# BV100011_ControlMemory.net
KiCad netlist of a schematic drawn in Altium Designer
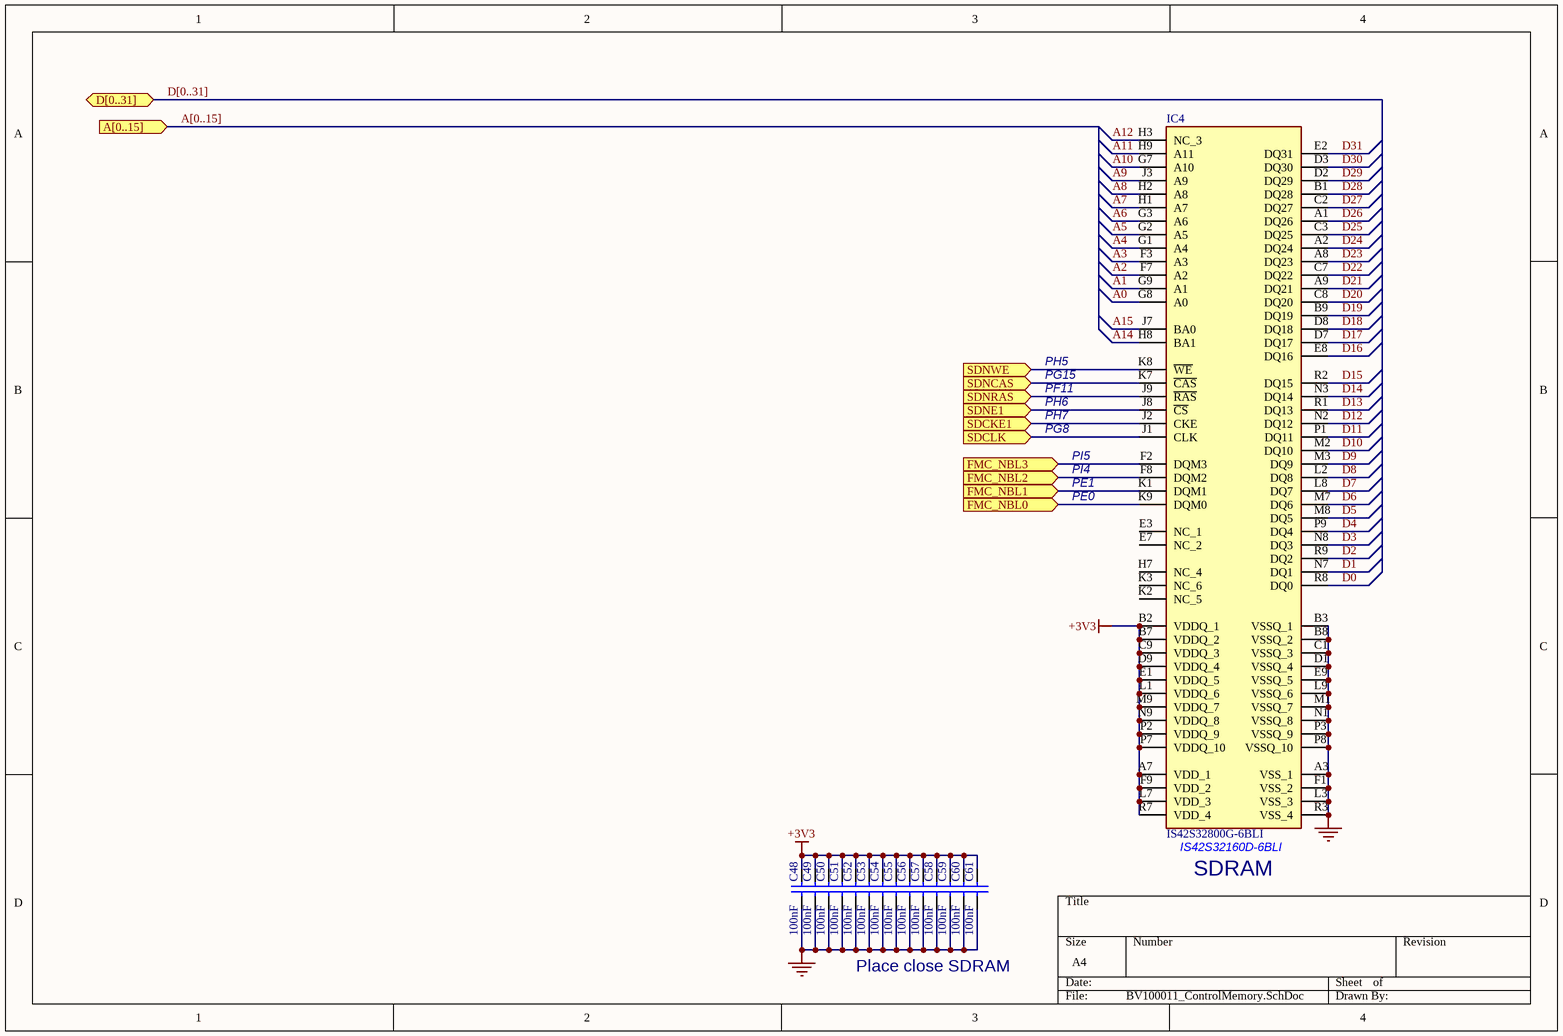
[diagram p0: BV100011_ControlMemory.SchDoc]

(export (version "E")
  (design (tool "Eeschema 10.0.6"))
  (components
    (comp (ref "C48")
      (value "100nF")
      (footprint "C0603")
      (description "Capacitor")
      (fields (field (name "PUBLISHER") "Altium Limited"))
      (libsource (lib "Miscellaneous Devices") (part "Cap"))
    )
    (comp (ref "C49")
      (value "100nF")
      (footprint "C0603")
      (description "Capacitor")
      (fields (field (name "PUBLISHER") "Altium Limited"))
      (libsource (lib "Miscellaneous Devices") (part "Cap"))
    )
    (comp (ref "C50")
      (value "100nF")
      (footprint "C0603")
      (description "Capacitor")
      (fields (field (name "PUBLISHER") "Altium Limited"))
      (libsource (lib "Miscellaneous Devices") (part "Cap"))
    )
    (comp (ref "C51")
      (value "100nF")
      (footprint "C0603")
      (description "Capacitor")
      (fields (field (name "PUBLISHER") "Altium Limited"))
      (libsource (lib "Miscellaneous Devices") (part "Cap"))
    )
    (comp (ref "C52")
      (value "100nF")
      (footprint "C0603")
      (description "Capacitor")
      (fields (field (name "PUBLISHER") "Altium Limited"))
      (libsource (lib "Miscellaneous Devices") (part "Cap"))
    )
    (comp (ref "C53")
      (value "100nF")
      (footprint "C0603")
      (description "Capacitor")
      (fields (field (name "PUBLISHER") "Altium Limited"))
      (libsource (lib "Miscellaneous Devices") (part "Cap"))
    )
    (comp (ref "C54")
      (value "100nF")
      (footprint "C0603")
      (description "Capacitor")
      (fields (field (name "PUBLISHER") "Altium Limited"))
      (libsource (lib "Miscellaneous Devices") (part "Cap"))
    )
    (comp (ref "C55")
      (value "100nF")
      (footprint "C0603")
      (description "Capacitor")
      (fields (field (name "PUBLISHER") "Altium Limited"))
      (libsource (lib "Miscellaneous Devices") (part "Cap"))
    )
    (comp (ref "C56")
      (value "100nF")
      (footprint "C0603")
      (description "Capacitor")
      (fields (field (name "PUBLISHER") "Altium Limited"))
      (libsource (lib "Miscellaneous Devices") (part "Cap"))
    )
    (comp (ref "C57")
      (value "100nF")
      (footprint "C0603")
      (description "Capacitor")
      (fields (field (name "PUBLISHER") "Altium Limited"))
      (libsource (lib "Miscellaneous Devices") (part "Cap"))
    )
    (comp (ref "C58")
      (value "100nF")
      (footprint "C0603")
      (description "Capacitor")
      (fields (field (name "PUBLISHER") "Altium Limited"))
      (libsource (lib "Miscellaneous Devices") (part "Cap"))
    )
    (comp (ref "C59")
      (value "100nF")
      (footprint "C0603")
      (description "Capacitor")
      (fields (field (name "PUBLISHER") "Altium Limited"))
      (libsource (lib "Miscellaneous Devices") (part "Cap"))
    )
    (comp (ref "C60")
      (value "100nF")
      (footprint "C0603")
      (description "Capacitor")
      (fields (field (name "PUBLISHER") "Altium Limited"))
      (libsource (lib "Miscellaneous Devices") (part "Cap"))
    )
    (comp (ref "C61")
      (value "100nF")
      (footprint "C0603")
      (description "Capacitor")
      (fields (field (name "PUBLISHER") "Altium Limited"))
      (libsource (lib "Miscellaneous Devices") (part "Cap"))
    )
    (comp (ref "IC4")
      (value "IS42S32800G-6BLI")
      (footprint "BGA90C80P9X15_800X1300X120")
      (description "Integrated Circuit")
      (fields (field (name "MOUSER PART NUMBER") "870-IS42S32800G-6BLI"))
      (libsource (lib "SamacSys") (part "IS42S32800G-6BLI"))
    )
  )
  (nets
    (net (code "2") (name "+3V3") (class "Default")
      (node (ref "C48") (pin "1") (pinfunction "1_1") (pintype "passive"))
      (node (ref "C49") (pin "1") (pinfunction "1_1") (pintype "passive"))
      (node (ref "C50") (pin "1") (pinfunction "1_1") (pintype "passive"))
      (node (ref "C51") (pin "1") (pinfunction "1_1") (pintype "passive"))
      (node (ref "C52") (pin "1") (pinfunction "1_1") (pintype "passive"))
      (node (ref "C53") (pin "1") (pinfunction "1_1") (pintype "passive"))
      (node (ref "C54") (pin "1") (pinfunction "1_1") (pintype "passive"))
      (node (ref "C55") (pin "1") (pinfunction "1_1") (pintype "passive"))
      (node (ref "C56") (pin "1") (pinfunction "1_1") (pintype "passive"))
      (node (ref "C57") (pin "1") (pinfunction "1_1") (pintype "passive"))
      (node (ref "C58") (pin "1") (pinfunction "1_1") (pintype "passive"))
      (node (ref "C59") (pin "1") (pinfunction "1_1") (pintype "passive"))
      (node (ref "C60") (pin "1") (pinfunction "1_1") (pintype "passive"))
      (node (ref "C61") (pin "1") (pinfunction "1_1") (pintype "passive"))
      (node (ref "IC4") (pin "A7") (pinfunction "VDD_1_A7") (pintype "passive"))
      (node (ref "IC4") (pin "B2") (pinfunction "VDDQ_1_B2") (pintype "passive"))
      (node (ref "IC4") (pin "B7") (pinfunction "VDDQ_2_B7") (pintype "passive"))
      (node (ref "IC4") (pin "C9") (pinfunction "VDDQ_3_C9") (pintype "passive"))
      (node (ref "IC4") (pin "D9") (pinfunction "VDDQ_4_D9") (pintype "passive"))
      (node (ref "IC4") (pin "E1") (pinfunction "VDDQ_5_E1") (pintype "passive"))
      (node (ref "IC4") (pin "F9") (pinfunction "VDD_2_F9") (pintype "passive"))
      (node (ref "IC4") (pin "L1") (pinfunction "VDDQ_6_L1") (pintype "passive"))
      (node (ref "IC4") (pin "L7") (pinfunction "VDD_3_L7") (pintype "passive"))
      (node (ref "IC4") (pin "M9") (pinfunction "VDDQ_7_M9") (pintype "passive"))
      (node (ref "IC4") (pin "N9") (pinfunction "VDDQ_8_N9") (pintype "passive"))
      (node (ref "IC4") (pin "P2") (pinfunction "VDDQ_9_P2") (pintype "passive"))
      (node (ref "IC4") (pin "P7") (pinfunction "VDDQ_10_P7") (pintype "passive"))
      (node (ref "IC4") (pin "R7") (pinfunction "VDD_4_R7") (pintype "passive"))
    )
    (net (code "3") (name "/A0") (class "Default")
      (node (ref "IC4") (pin "G8") (pinfunction "A0_G8") (pintype "passive"))
    )
    (net (code "4") (name "/A1") (class "Default")
      (node (ref "IC4") (pin "G9") (pinfunction "A1_G9") (pintype "passive"))
    )
    (net (code "5") (name "/A2") (class "Default")
      (node (ref "IC4") (pin "F7") (pinfunction "A2_F7") (pintype "passive"))
    )
    (net (code "6") (name "/A3") (class "Default")
      (node (ref "IC4") (pin "F3") (pinfunction "A3_F3") (pintype "passive"))
    )
    (net (code "7") (name "/A4") (class "Default")
      (node (ref "IC4") (pin "G1") (pinfunction "A4_G1") (pintype "passive"))
    )
    (net (code "8") (name "/A5") (class "Default")
      (node (ref "IC4") (pin "G2") (pinfunction "A5_G2") (pintype "passive"))
    )
    (net (code "9") (name "/A6") (class "Default")
      (node (ref "IC4") (pin "G3") (pinfunction "A6_G3") (pintype "passive"))
    )
    (net (code "10") (name "/A7") (class "Default")
      (node (ref "IC4") (pin "H1") (pinfunction "A7_H1") (pintype "passive"))
    )
    (net (code "11") (name "/A8") (class "Default")
      (node (ref "IC4") (pin "H2") (pinfunction "A8_H2") (pintype "passive"))
    )
    (net (code "12") (name "/A9") (class "Default")
      (node (ref "IC4") (pin "J3") (pinfunction "A9_J3") (pintype "passive"))
    )
    (net (code "13") (name "/A10") (class "Default")
      (node (ref "IC4") (pin "G7") (pinfunction "A10_G7") (pintype "passive"))
    )
    (net (code "14") (name "/A11") (class "Default")
      (node (ref "IC4") (pin "H9") (pinfunction "A11_H9") (pintype "passive"))
    )
    (net (code "15") (name "/A12") (class "Default")
      (node (ref "IC4") (pin "H3") (pinfunction "NC_3_H3") (pintype "passive"))
    )
    (net (code "16") (name "/A14") (class "Default")
      (node (ref "IC4") (pin "H8") (pinfunction "BA1_H8") (pintype "passive"))
    )
    (net (code "17") (name "/A15") (class "Default")
      (node (ref "IC4") (pin "J7") (pinfunction "BA0_J7") (pintype "passive"))
    )
    (net (code "19") (name "/D0") (class "Default")
      (node (ref "IC4") (pin "R8") (pinfunction "DQ0_R8") (pintype "passive"))
    )
    (net (code "20") (name "/D1") (class "Default")
      (node (ref "IC4") (pin "N7") (pinfunction "DQ1_N7") (pintype "passive"))
    )
    (net (code "21") (name "/D2") (class "Default")
      (node (ref "IC4") (pin "R9") (pinfunction "DQ2_R9") (pintype "passive"))
    )
    (net (code "22") (name "/D3") (class "Default")
      (node (ref "IC4") (pin "N8") (pinfunction "DQ3_N8") (pintype "passive"))
    )
    (net (code "23") (name "/D4") (class "Default")
      (node (ref "IC4") (pin "P9") (pinfunction "DQ4_P9") (pintype "passive"))
    )
    (net (code "24") (name "/D5") (class "Default")
      (node (ref "IC4") (pin "M8") (pinfunction "DQ5_M8") (pintype "passive"))
    )
    (net (code "25") (name "/D6") (class "Default")
      (node (ref "IC4") (pin "M7") (pinfunction "DQ6_M7") (pintype "passive"))
    )
    (net (code "26") (name "/D7") (class "Default")
      (node (ref "IC4") (pin "L8") (pinfunction "DQ7_L8") (pintype "passive"))
    )
    (net (code "27") (name "/D8") (class "Default")
      (node (ref "IC4") (pin "L2") (pinfunction "DQ8_L2") (pintype "passive"))
    )
    (net (code "28") (name "/D9") (class "Default")
      (node (ref "IC4") (pin "M3") (pinfunction "DQ9_M3") (pintype "passive"))
    )
    (net (code "29") (name "/D10") (class "Default")
      (node (ref "IC4") (pin "M2") (pinfunction "DQ10_M2") (pintype "passive"))
    )
    (net (code "30") (name "/D11") (class "Default")
      (node (ref "IC4") (pin "P1") (pinfunction "DQ11_P1") (pintype "passive"))
    )
    (net (code "31") (name "/D12") (class "Default")
      (node (ref "IC4") (pin "N2") (pinfunction "DQ12_N2") (pintype "passive"))
    )
    (net (code "32") (name "/D13") (class "Default")
      (node (ref "IC4") (pin "R1") (pinfunction "DQ13_R1") (pintype "passive"))
    )
    (net (code "33") (name "/D14") (class "Default")
      (node (ref "IC4") (pin "N3") (pinfunction "DQ14_N3") (pintype "passive"))
    )
    (net (code "34") (name "/D15") (class "Default")
      (node (ref "IC4") (pin "R2") (pinfunction "DQ15_R2") (pintype "passive"))
    )
    (net (code "35") (name "/D16") (class "Default")
      (node (ref "IC4") (pin "E8") (pinfunction "DQ16_E8") (pintype "passive"))
    )
    (net (code "36") (name "/D17") (class "Default")
      (node (ref "IC4") (pin "D7") (pinfunction "DQ17_D7") (pintype "passive"))
    )
    (net (code "37") (name "/D18") (class "Default")
      (node (ref "IC4") (pin "D8") (pinfunction "DQ18_D8") (pintype "passive"))
    )
    (net (code "38") (name "/D19") (class "Default")
      (node (ref "IC4") (pin "B9") (pinfunction "DQ19_B9") (pintype "passive"))
    )
    (net (code "39") (name "/D20") (class "Default")
      (node (ref "IC4") (pin "C8") (pinfunction "DQ20_C8") (pintype "passive"))
    )
    (net (code "40") (name "/D21") (class "Default")
      (node (ref "IC4") (pin "A9") (pinfunction "DQ21_A9") (pintype "passive"))
    )
    (net (code "41") (name "/D22") (class "Default")
      (node (ref "IC4") (pin "C7") (pinfunction "DQ22_C7") (pintype "passive"))
    )
    (net (code "42") (name "/D23") (class "Default")
      (node (ref "IC4") (pin "A8") (pinfunction "DQ23_A8") (pintype "passive"))
    )
    (net (code "43") (name "/D24") (class "Default")
      (node (ref "IC4") (pin "A2") (pinfunction "DQ24_A2") (pintype "passive"))
    )
    (net (code "44") (name "/D25") (class "Default")
      (node (ref "IC4") (pin "C3") (pinfunction "DQ25_C3") (pintype "passive"))
    )
    (net (code "45") (name "/D26") (class "Default")
      (node (ref "IC4") (pin "A1") (pinfunction "DQ26_A1") (pintype "passive"))
    )
    (net (code "46") (name "/D27") (class "Default")
      (node (ref "IC4") (pin "C2") (pinfunction "DQ27_C2") (pintype "passive"))
    )
    (net (code "47") (name "/D28") (class "Default")
      (node (ref "IC4") (pin "B1") (pinfunction "DQ28_B1") (pintype "passive"))
    )
    (net (code "48") (name "/D29") (class "Default")
      (node (ref "IC4") (pin "D2") (pinfunction "DQ29_D2") (pintype "passive"))
    )
    (net (code "49") (name "/D30") (class "Default")
      (node (ref "IC4") (pin "D3") (pinfunction "DQ30_D3") (pintype "passive"))
    )
    (net (code "50") (name "/D31") (class "Default")
      (node (ref "IC4") (pin "E2") (pinfunction "DQ31_E2") (pintype "passive"))
    )
    (net (code "52") (name "/FMC_NBL0") (class "Default")
      (node (ref "IC4") (pin "K9") (pinfunction "DQM0_K9") (pintype "passive"))
    )
    (net (code "53") (name "/FMC_NBL1") (class "Default")
      (node (ref "IC4") (pin "K1") (pinfunction "DQM1_K1") (pintype "passive"))
    )
    (net (code "54") (name "/FMC_NBL2") (class "Default")
      (node (ref "IC4") (pin "F8") (pinfunction "DQM2_F8") (pintype "passive"))
    )
    (net (code "55") (name "/FMC_NBL3") (class "Default")
      (node (ref "IC4") (pin "F2") (pinfunction "DQM3_F2") (pintype "passive"))
    )
    (net (code "56") (name "/SDCKE1") (class "Default")
      (node (ref "IC4") (pin "J2") (pinfunction "CKE_J2") (pintype "passive"))
    )
    (net (code "57") (name "/SDCLK") (class "Default")
      (node (ref "IC4") (pin "J1") (pinfunction "CLK_J1") (pintype "passive"))
    )
    (net (code "58") (name "/SDNCAS") (class "Default")
      (node (ref "IC4") (pin "K7") (pinfunction "~{CAS}_K7") (pintype "passive"))
    )
    (net (code "59") (name "/SDNE1") (class "Default")
      (node (ref "IC4") (pin "J8") (pinfunction "~{CS}_J8") (pintype "passive"))
    )
    (net (code "60") (name "/SDNRAS") (class "Default")
      (node (ref "IC4") (pin "J9") (pinfunction "~{RAS}_J9") (pintype "passive"))
    )
    (net (code "61") (name "/SDNWE") (class "Default")
      (node (ref "IC4") (pin "K8") (pinfunction "~{WE}_K8") (pintype "passive"))
    )
    (net (code "62") (name "GND") (class "Default")
      (node (ref "C48") (pin "2") (pinfunction "2_2") (pintype "passive"))
      (node (ref "C49") (pin "2") (pinfunction "2_2") (pintype "passive"))
      (node (ref "C50") (pin "2") (pinfunction "2_2") (pintype "passive"))
      (node (ref "C51") (pin "2") (pinfunction "2_2") (pintype "passive"))
      (node (ref "C52") (pin "2") (pinfunction "2_2") (pintype "passive"))
      (node (ref "C53") (pin "2") (pinfunction "2_2") (pintype "passive"))
      (node (ref "C54") (pin "2") (pinfunction "2_2") (pintype "passive"))
      (node (ref "C55") (pin "2") (pinfunction "2_2") (pintype "passive"))
      (node (ref "C56") (pin "2") (pinfunction "2_2") (pintype "passive"))
      (node (ref "C57") (pin "2") (pinfunction "2_2") (pintype "passive"))
      (node (ref "C58") (pin "2") (pinfunction "2_2") (pintype "passive"))
      (node (ref "C59") (pin "2") (pinfunction "2_2") (pintype "passive"))
      (node (ref "C60") (pin "2") (pinfunction "2_2") (pintype "passive"))
      (node (ref "C61") (pin "2") (pinfunction "2_2") (pintype "passive"))
      (node (ref "IC4") (pin "A3") (pinfunction "VSS_1_A3") (pintype "passive"))
      (node (ref "IC4") (pin "B3") (pinfunction "VSSQ_1_B3") (pintype "passive"))
      (node (ref "IC4") (pin "B8") (pinfunction "VSSQ_2_B8") (pintype "passive"))
      (node (ref "IC4") (pin "C1") (pinfunction "VSSQ_3_C1") (pintype "passive"))
      (node (ref "IC4") (pin "D1") (pinfunction "VSSQ_4_D1") (pintype "passive"))
      (node (ref "IC4") (pin "E9") (pinfunction "VSSQ_5_E9") (pintype "passive"))
      (node (ref "IC4") (pin "F1") (pinfunction "VSS_2_F1") (pintype "passive"))
      (node (ref "IC4") (pin "L3") (pinfunction "VSS_3_L3") (pintype "passive"))
      (node (ref "IC4") (pin "L9") (pinfunction "VSSQ_6_L9") (pintype "passive"))
      (node (ref "IC4") (pin "M1") (pinfunction "VSSQ_7_M1") (pintype "passive"))
      (node (ref "IC4") (pin "N1") (pinfunction "VSSQ_8_N1") (pintype "passive"))
      (node (ref "IC4") (pin "P3") (pinfunction "VSSQ_9_P3") (pintype "passive"))
      (node (ref "IC4") (pin "P8") (pinfunction "VSSQ_10_P8") (pintype "passive"))
      (node (ref "IC4") (pin "R3") (pinfunction "VSS_4_R3") (pintype "passive"))
    )
    (net (code "63") (name "unconnected-(IC4-NC_1-PadE3)") (class "Default")
      (node (ref "IC4") (pin "E3") (pinfunction "NC_1_E3") (pintype "passive"))
    )
    (net (code "64") (name "unconnected-(IC4-NC_2-PadE7)") (class "Default")
      (node (ref "IC4") (pin "E7") (pinfunction "NC_2_E7") (pintype "passive"))
    )
    (net (code "65") (name "unconnected-(IC4-NC_4-PadH7)") (class "Default")
      (node (ref "IC4") (pin "H7") (pinfunction "NC_4_H7") (pintype "passive"))
    )
    (net (code "66") (name "unconnected-(IC4-NC_5-PadK2)") (class "Default")
      (node (ref "IC4") (pin "K2") (pinfunction "NC_5_K2") (pintype "passive"))
    )
    (net (code "67") (name "unconnected-(IC4-NC_6-PadK3)") (class "Default")
      (node (ref "IC4") (pin "K3") (pinfunction "NC_6_K3") (pintype "passive"))
    )
  )
)
